# klmag2gend-b031.net
KiCad netlist of a schematic drawn in Altium Designer
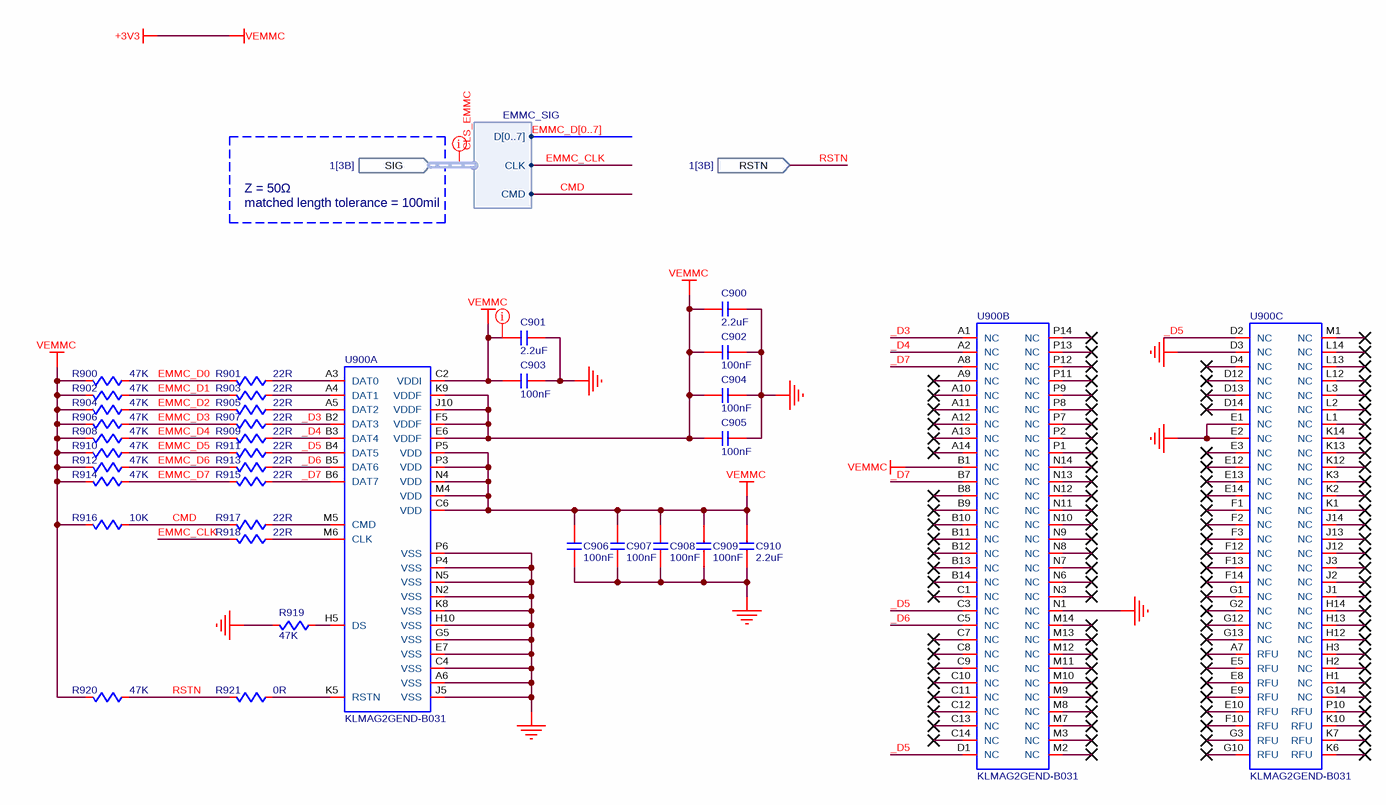
[diagram p0: klmag2gend-b031.SchDoc]

(export (version "E")
  (design (tool "Eeschema 10.0.6"))
  (components
    (comp (ref "C900")
      (value "2.2uF")
      (footprint "mw:C0603")
      (fields (field (name "VOLTAGE") "25V") (field (name "Comment") "C-NOMO"))
      (libsource (lib "mw") (part "C-NOMO"))
    )
    (comp (ref "C901")
      (value "2.2uF")
      (footprint "mw:C0603")
      (fields (field (name "VOLTAGE") "25V") (field (name "Comment") "C-NOMO"))
      (libsource (lib "mw") (part "C-NOMO"))
    )
    (comp (ref "C902")
      (value "100nF")
      (footprint "mw:C0402")
      (fields (field (name "VOLTAGE") "25V") (field (name "Comment") "C-NOMO"))
      (libsource (lib "mw") (part "C-NOMO"))
    )
    (comp (ref "C903")
      (value "100nF")
      (footprint "mw:C0402")
      (fields (field (name "VOLTAGE") "25V") (field (name "Comment") "C-NOMO"))
      (libsource (lib "mw") (part "C-NOMO"))
    )
    (comp (ref "C904")
      (value "100nF")
      (footprint "mw:C0402")
      (fields (field (name "VOLTAGE") "25V") (field (name "Comment") "C-NOMO"))
      (libsource (lib "mw") (part "C-NOMO"))
    )
    (comp (ref "C905")
      (value "100nF")
      (footprint "mw:C0402")
      (fields (field (name "VOLTAGE") "25V") (field (name "Comment") "C-NOMO"))
      (libsource (lib "mw") (part "C-NOMO"))
    )
    (comp (ref "C906")
      (value "100nF")
      (footprint "mw:C0402")
      (fields (field (name "VOLTAGE") "25V") (field (name "Comment") "C-NOMO"))
      (libsource (lib "mw") (part "C-NOMO"))
    )
    (comp (ref "C907")
      (value "100nF")
      (footprint "mw:C0402")
      (fields (field (name "VOLTAGE") "25V") (field (name "Comment") "C-NOMO"))
      (libsource (lib "mw") (part "C-NOMO"))
    )
    (comp (ref "C908")
      (value "100nF")
      (footprint "mw:C0402")
      (fields (field (name "VOLTAGE") "25V") (field (name "Comment") "C-NOMO"))
      (libsource (lib "mw") (part "C-NOMO"))
    )
    (comp (ref "C909")
      (value "100nF")
      (footprint "mw:C0402")
      (fields (field (name "VOLTAGE") "25V") (field (name "Comment") "C-NOMO"))
      (libsource (lib "mw") (part "C-NOMO"))
    )
    (comp (ref "C910")
      (value "2.2uF")
      (footprint "mw:C0603")
      (fields (field (name "VOLTAGE") "25V") (field (name "Comment") "C-NOMO"))
      (libsource (lib "mw") (part "C-NOMO"))
    )
    (comp (ref "R900")
      (value "47K")
      (footprint "mw:R0402")
      (fields (field (name "Comment") "R"))
      (libsource (lib "mw") (part "R"))
    )
    (comp (ref "R901")
      (value "22R")
      (footprint "mw:R0402")
      (fields (field (name "Comment") "R"))
      (libsource (lib "mw") (part "R"))
    )
    (comp (ref "R902")
      (value "47K")
      (footprint "mw:R0402")
      (fields (field (name "Comment") "R"))
      (libsource (lib "mw") (part "R"))
    )
    (comp (ref "R903")
      (value "22R")
      (footprint "mw:R0402")
      (fields (field (name "Comment") "R"))
      (libsource (lib "mw") (part "R"))
    )
    (comp (ref "R904")
      (value "47K")
      (footprint "mw:R0402")
      (fields (field (name "Comment") "R"))
      (libsource (lib "mw") (part "R"))
    )
    (comp (ref "R905")
      (value "22R")
      (footprint "mw:R0402")
      (fields (field (name "Comment") "R"))
      (libsource (lib "mw") (part "R"))
    )
    (comp (ref "R906")
      (value "47K")
      (footprint "mw:R0402")
      (fields (field (name "Comment") "R"))
      (libsource (lib "mw") (part "R"))
    )
    (comp (ref "R907")
      (value "22R")
      (footprint "mw:R0402")
      (fields (field (name "Comment") "R"))
      (libsource (lib "mw") (part "R"))
    )
    (comp (ref "R908")
      (value "47K")
      (footprint "mw:R0402")
      (fields (field (name "Comment") "R"))
      (libsource (lib "mw") (part "R"))
    )
    (comp (ref "R909")
      (value "22R")
      (footprint "mw:R0402")
      (fields (field (name "Comment") "R"))
      (libsource (lib "mw") (part "R"))
    )
    (comp (ref "R910")
      (value "47K")
      (footprint "mw:R0402")
      (fields (field (name "Comment") "R"))
      (libsource (lib "mw") (part "R"))
    )
    (comp (ref "R911")
      (value "22R")
      (footprint "mw:R0402")
      (fields (field (name "Comment") "R"))
      (libsource (lib "mw") (part "R"))
    )
    (comp (ref "R912")
      (value "47K")
      (footprint "mw:R0402")
      (fields (field (name "Comment") "R"))
      (libsource (lib "mw") (part "R"))
    )
    (comp (ref "R913")
      (value "22R")
      (footprint "mw:R0402")
      (fields (field (name "Comment") "R"))
      (libsource (lib "mw") (part "R"))
    )
    (comp (ref "R914")
      (value "47K")
      (footprint "mw:R0402")
      (fields (field (name "Comment") "R"))
      (libsource (lib "mw") (part "R"))
    )
    (comp (ref "R915")
      (value "22R")
      (footprint "mw:R0402")
      (fields (field (name "Comment") "R"))
      (libsource (lib "mw") (part "R"))
    )
    (comp (ref "R916")
      (value "10K")
      (footprint "mw:R0402")
      (fields (field (name "Comment") "R"))
      (libsource (lib "mw") (part "R"))
    )
    (comp (ref "R917")
      (value "22R")
      (footprint "mw:R0402")
      (fields (field (name "Comment") "R"))
      (libsource (lib "mw") (part "R"))
    )
    (comp (ref "R918")
      (value "22R")
      (footprint "mw:R0402")
      (fields (field (name "Comment") "R"))
      (libsource (lib "mw") (part "R"))
    )
    (comp (ref "R919")
      (value "47K")
      (footprint "mw:R0402")
      (fields (field (name "Comment") "R"))
      (libsource (lib "mw") (part "R"))
    )
    (comp (ref "R920")
      (value "47K")
      (footprint "mw:R0402")
      (fields (field (name "Comment") "R"))
      (libsource (lib "mw") (part "R"))
    )
    (comp (ref "R921")
      (value "0R")
      (footprint "mw:R0402")
      (fields (field (name "Comment") "R"))
      (libsource (lib "mw") (part "R"))
    )
    (comp (ref "U900")
      (value "KLMAG2GEND-B031")
      (footprint "mw:KLMAG2GEND-B031")
      (description "EMMC")
      (libsource (lib "mw") (part "KLMAG2GEND-B031"))
    )
  )
  (nets
    (net (code "2") (name "+3V3") (class "Default")
      (node (ref "C900") (pin "2") (pinfunction "2_2") (pintype "passive"))
      (node (ref "C901") (pin "2") (pinfunction "2_2") (pintype "passive"))
      (node (ref "C902") (pin "2") (pinfunction "2_2") (pintype "passive"))
      (node (ref "C903") (pin "2") (pinfunction "2_2") (pintype "passive"))
      (node (ref "C904") (pin "2") (pinfunction "2_2") (pintype "passive"))
      (node (ref "C905") (pin "2") (pinfunction "2_2") (pintype "passive"))
      (node (ref "C906") (pin "2") (pinfunction "2_2") (pintype "passive"))
      (node (ref "C907") (pin "2") (pinfunction "2_2") (pintype "passive"))
      (node (ref "C908") (pin "2") (pinfunction "2_2") (pintype "passive"))
      (node (ref "C909") (pin "2") (pinfunction "2_2") (pintype "passive"))
      (node (ref "C910") (pin "2") (pinfunction "2_2") (pintype "passive"))
      (node (ref "R900") (pin "1") (pinfunction "1_1") (pintype "passive"))
      (node (ref "R902") (pin "1") (pinfunction "1_1") (pintype "passive"))
      (node (ref "R904") (pin "1") (pinfunction "1_1") (pintype "passive"))
      (node (ref "R906") (pin "1") (pinfunction "1_1") (pintype "passive"))
      (node (ref "R908") (pin "1") (pinfunction "1_1") (pintype "passive"))
      (node (ref "R910") (pin "1") (pinfunction "1_1") (pintype "passive"))
      (node (ref "R912") (pin "1") (pinfunction "1_1") (pintype "passive"))
      (node (ref "R914") (pin "1") (pinfunction "1_1") (pintype "passive"))
      (node (ref "R916") (pin "1") (pinfunction "1_1") (pintype "passive"))
      (node (ref "R920") (pin "1") (pinfunction "1_1") (pintype "passive"))
      (node (ref "U900") (pin "B1") (pinfunction "NC_B1") (pintype "passive"))
      (node (ref "U900") (pin "C2") (pinfunction "VDDI_C2") (pintype "passive"))
      (node (ref "U900") (pin "C6") (pinfunction "VDD_C6") (pintype "passive"))
      (node (ref "U900") (pin "E6") (pinfunction "VDDF_E6") (pintype "passive"))
      (node (ref "U900") (pin "F5") (pinfunction "VDDF_F5") (pintype "passive"))
      (node (ref "U900") (pin "J10") (pinfunction "VDDF_J10") (pintype "passive"))
      (node (ref "U900") (pin "K9") (pinfunction "VDDF_K9") (pintype "passive"))
      (node (ref "U900") (pin "M4") (pinfunction "VDD_M4") (pintype "passive"))
      (node (ref "U900") (pin "N4") (pinfunction "VDD_N4") (pintype "passive"))
      (node (ref "U900") (pin "P3") (pinfunction "VDD_P3") (pintype "passive"))
      (node (ref "U900") (pin "P5") (pinfunction "VDD_P5") (pintype "passive"))
    )
    (net (code "3") (name "/CMD") (class "Default")
      (node (ref "R916") (pin "2") (pinfunction "2_2") (pintype "passive"))
      (node (ref "R917") (pin "1") (pinfunction "1_1") (pintype "passive"))
    )
    (net (code "4") (name "/EMMC_CLK") (class "Default")
      (node (ref "R918") (pin "1") (pinfunction "1_1") (pintype "passive"))
    )
    (net (code "5") (name "/EMMC_D0") (class "Default")
      (node (ref "R900") (pin "2") (pinfunction "2_2") (pintype "passive"))
      (node (ref "R901") (pin "1") (pinfunction "1_1") (pintype "passive"))
    )
    (net (code "6") (name "/EMMC_D1") (class "Default")
      (node (ref "R902") (pin "2") (pinfunction "2_2") (pintype "passive"))
      (node (ref "R903") (pin "1") (pinfunction "1_1") (pintype "passive"))
    )
    (net (code "7") (name "/EMMC_D2") (class "Default")
      (node (ref "R904") (pin "2") (pinfunction "2_2") (pintype "passive"))
      (node (ref "R905") (pin "1") (pinfunction "1_1") (pintype "passive"))
    )
    (net (code "8") (name "/EMMC_D3") (class "Default")
      (node (ref "R906") (pin "2") (pinfunction "2_2") (pintype "passive"))
      (node (ref "R907") (pin "1") (pinfunction "1_1") (pintype "passive"))
    )
    (net (code "9") (name "/EMMC_D4") (class "Default")
      (node (ref "R908") (pin "2") (pinfunction "2_2") (pintype "passive"))
      (node (ref "R909") (pin "1") (pinfunction "1_1") (pintype "passive"))
    )
    (net (code "10") (name "/EMMC_D5") (class "Default")
      (node (ref "R910") (pin "2") (pinfunction "2_2") (pintype "passive"))
      (node (ref "R911") (pin "1") (pinfunction "1_1") (pintype "passive"))
    )
    (net (code "11") (name "/EMMC_D6") (class "Default")
      (node (ref "R912") (pin "2") (pinfunction "2_2") (pintype "passive"))
      (node (ref "R913") (pin "1") (pinfunction "1_1") (pintype "passive"))
    )
    (net (code "12") (name "/EMMC_D7") (class "Default")
      (node (ref "R914") (pin "2") (pinfunction "2_2") (pintype "passive"))
      (node (ref "R915") (pin "1") (pinfunction "1_1") (pintype "passive"))
    )
    (net (code "13") (name "/RSTN") (class "Default")
      (node (ref "R920") (pin "2") (pinfunction "2_2") (pintype "passive"))
      (node (ref "R921") (pin "1") (pinfunction "1_1") (pintype "passive"))
    )
    (net (code "15") (name "/_D3") (class "Default")
      (node (ref "R907") (pin "2") (pinfunction "2_2") (pintype "passive"))
      (node (ref "U900") (pin "A1") (pinfunction "NC_A1") (pintype "passive"))
      (node (ref "U900") (pin "B2") (pinfunction "DAT3_B2") (pintype "passive"))
    )
    (net (code "16") (name "/_D4") (class "Default")
      (node (ref "R909") (pin "2") (pinfunction "2_2") (pintype "passive"))
      (node (ref "U900") (pin "A2") (pinfunction "NC_A2") (pintype "passive"))
      (node (ref "U900") (pin "B3") (pinfunction "DAT4_B3") (pintype "passive"))
    )
    (net (code "17") (name "/_D5") (class "Default")
      (node (ref "R911") (pin "2") (pinfunction "2_2") (pintype "passive"))
      (node (ref "U900") (pin "B4") (pinfunction "DAT5_B4") (pintype "passive"))
      (node (ref "U900") (pin "C3") (pinfunction "NC_C3") (pintype "passive"))
      (node (ref "U900") (pin "D1") (pinfunction "NC_D1") (pintype "passive"))
      (node (ref "U900") (pin "D2") (pinfunction "NC_D2") (pintype "passive"))
    )
    (net (code "18") (name "/_D6") (class "Default")
      (node (ref "R913") (pin "2") (pinfunction "2_2") (pintype "passive"))
      (node (ref "U900") (pin "B5") (pinfunction "DAT6_B5") (pintype "passive"))
      (node (ref "U900") (pin "C5") (pinfunction "NC_C5") (pintype "passive"))
    )
    (net (code "19") (name "/_D7") (class "Default")
      (node (ref "R915") (pin "2") (pinfunction "2_2") (pintype "passive"))
      (node (ref "U900") (pin "A8") (pinfunction "NC_A8") (pintype "passive"))
      (node (ref "U900") (pin "B6") (pinfunction "DAT7_B6") (pintype "passive"))
      (node (ref "U900") (pin "B7") (pinfunction "NC_B7") (pintype "passive"))
    )
    (net (code "21") (name "GND") (class "Default")
      (node (ref "C900") (pin "1") (pinfunction "1_1") (pintype "passive"))
      (node (ref "C901") (pin "1") (pinfunction "1_1") (pintype "passive"))
      (node (ref "C902") (pin "1") (pinfunction "1_1") (pintype "passive"))
      (node (ref "C903") (pin "1") (pinfunction "1_1") (pintype "passive"))
      (node (ref "C904") (pin "1") (pinfunction "1_1") (pintype "passive"))
      (node (ref "C905") (pin "1") (pinfunction "1_1") (pintype "passive"))
      (node (ref "C906") (pin "1") (pinfunction "1_1") (pintype "passive"))
      (node (ref "C907") (pin "1") (pinfunction "1_1") (pintype "passive"))
      (node (ref "C908") (pin "1") (pinfunction "1_1") (pintype "passive"))
      (node (ref "C909") (pin "1") (pinfunction "1_1") (pintype "passive"))
      (node (ref "C910") (pin "1") (pinfunction "1_1") (pintype "passive"))
      (node (ref "R919") (pin "1") (pinfunction "1_1") (pintype "passive"))
      (node (ref "U900") (pin "A6") (pinfunction "VSS_A6") (pintype "passive"))
      (node (ref "U900") (pin "C4") (pinfunction "VSS_C4") (pintype "passive"))
      (node (ref "U900") (pin "D3") (pinfunction "NC_D3") (pintype "passive"))
      (node (ref "U900") (pin "E1") (pinfunction "NC_E1") (pintype "passive"))
      (node (ref "U900") (pin "E2") (pinfunction "NC_E2") (pintype "passive"))
      (node (ref "U900") (pin "E7") (pinfunction "VSS_E7") (pintype "passive"))
      (node (ref "U900") (pin "G5") (pinfunction "VSS_G5") (pintype "passive"))
      (node (ref "U900") (pin "H10") (pinfunction "VSS_H10") (pintype "passive"))
      (node (ref "U900") (pin "J5") (pinfunction "VSS_J5") (pintype "passive"))
      (node (ref "U900") (pin "K8") (pinfunction "VSS_K8") (pintype "passive"))
      (node (ref "U900") (pin "N1") (pinfunction "NC_N1") (pintype "passive"))
      (node (ref "U900") (pin "N2") (pinfunction "VSS_N2") (pintype "passive"))
      (node (ref "U900") (pin "N5") (pinfunction "VSS_N5") (pintype "passive"))
      (node (ref "U900") (pin "P4") (pinfunction "VSS_P4") (pintype "passive"))
      (node (ref "U900") (pin "P6") (pinfunction "VSS_P6") (pintype "passive"))
    )
    (net (code "22") (name "Net-(U900A-CLK)") (class "Default")
      (node (ref "R918") (pin "2") (pinfunction "2_2") (pintype "passive"))
      (node (ref "U900") (pin "M6") (pinfunction "CLK_M6") (pintype "passive"))
    )
    (net (code "23") (name "Net-(U900A-CMD)") (class "Default")
      (node (ref "R917") (pin "2") (pinfunction "2_2") (pintype "passive"))
      (node (ref "U900") (pin "M5") (pinfunction "CMD_M5") (pintype "passive"))
    )
    (net (code "24") (name "Net-(U900A-DAT0)") (class "Default")
      (node (ref "R901") (pin "2") (pinfunction "2_2") (pintype "passive"))
      (node (ref "U900") (pin "A3") (pinfunction "DAT0_A3") (pintype "passive"))
    )
    (net (code "25") (name "Net-(U900A-DAT1)") (class "Default")
      (node (ref "R903") (pin "2") (pinfunction "2_2") (pintype "passive"))
      (node (ref "U900") (pin "A4") (pinfunction "DAT1_A4") (pintype "passive"))
    )
    (net (code "26") (name "Net-(U900A-DAT2)") (class "Default")
      (node (ref "R905") (pin "2") (pinfunction "2_2") (pintype "passive"))
      (node (ref "U900") (pin "A5") (pinfunction "DAT2_A5") (pintype "passive"))
    )
    (net (code "27") (name "Net-(U900A-DS)") (class "Default")
      (node (ref "R919") (pin "2") (pinfunction "2_2") (pintype "passive"))
      (node (ref "U900") (pin "H5") (pinfunction "DS_H5") (pintype "passive"))
    )
    (net (code "28") (name "Net-(U900A-RSTN)") (class "Default")
      (node (ref "R921") (pin "2") (pinfunction "2_2") (pintype "passive"))
      (node (ref "U900") (pin "K5") (pinfunction "RSTN_K5") (pintype "passive"))
    )
    (net (code "29") (name "unconnected-(U900B-NC-PadA9)") (class "Default")
      (node (ref "U900") (pin "A9") (pinfunction "NC_A9") (pintype "passive+no_connect"))
    )
    (net (code "30") (name "unconnected-(U900B-NC-PadA10)") (class "Default")
      (node (ref "U900") (pin "A10") (pinfunction "NC_A10") (pintype "passive+no_connect"))
    )
    (net (code "31") (name "unconnected-(U900B-NC-PadA11)") (class "Default")
      (node (ref "U900") (pin "A11") (pinfunction "NC_A11") (pintype "passive+no_connect"))
    )
    (net (code "32") (name "unconnected-(U900B-NC-PadA12)") (class "Default")
      (node (ref "U900") (pin "A12") (pinfunction "NC_A12") (pintype "passive+no_connect"))
    )
    (net (code "33") (name "unconnected-(U900B-NC-PadA13)") (class "Default")
      (node (ref "U900") (pin "A13") (pinfunction "NC_A13") (pintype "passive+no_connect"))
    )
    (net (code "34") (name "unconnected-(U900B-NC-PadA14)") (class "Default")
      (node (ref "U900") (pin "A14") (pinfunction "NC_A14") (pintype "passive+no_connect"))
    )
    (net (code "35") (name "unconnected-(U900B-NC-PadB8)") (class "Default")
      (node (ref "U900") (pin "B8") (pinfunction "NC_B8") (pintype "passive+no_connect"))
    )
    (net (code "36") (name "unconnected-(U900B-NC-PadB9)") (class "Default")
      (node (ref "U900") (pin "B9") (pinfunction "NC_B9") (pintype "passive+no_connect"))
    )
    (net (code "37") (name "unconnected-(U900B-NC-PadB10)") (class "Default")
      (node (ref "U900") (pin "B10") (pinfunction "NC_B10") (pintype "passive+no_connect"))
    )
    (net (code "38") (name "unconnected-(U900B-NC-PadB11)") (class "Default")
      (node (ref "U900") (pin "B11") (pinfunction "NC_B11") (pintype "passive+no_connect"))
    )
    (net (code "39") (name "unconnected-(U900B-NC-PadB12)") (class "Default")
      (node (ref "U900") (pin "B12") (pinfunction "NC_B12") (pintype "passive+no_connect"))
    )
    (net (code "40") (name "unconnected-(U900B-NC-PadB13)") (class "Default")
      (node (ref "U900") (pin "B13") (pinfunction "NC_B13") (pintype "passive+no_connect"))
    )
    (net (code "41") (name "unconnected-(U900B-NC-PadB14)") (class "Default")
      (node (ref "U900") (pin "B14") (pinfunction "NC_B14") (pintype "passive+no_connect"))
    )
    (net (code "42") (name "unconnected-(U900B-NC-PadC1)") (class "Default")
      (node (ref "U900") (pin "C1") (pinfunction "NC_C1") (pintype "passive+no_connect"))
    )
    (net (code "43") (name "unconnected-(U900B-NC-PadC7)") (class "Default")
      (node (ref "U900") (pin "C7") (pinfunction "NC_C7") (pintype "passive+no_connect"))
    )
    (net (code "44") (name "unconnected-(U900B-NC-PadC8)") (class "Default")
      (node (ref "U900") (pin "C8") (pinfunction "NC_C8") (pintype "passive+no_connect"))
    )
    (net (code "45") (name "unconnected-(U900B-NC-PadC9)") (class "Default")
      (node (ref "U900") (pin "C9") (pinfunction "NC_C9") (pintype "passive+no_connect"))
    )
    (net (code "46") (name "unconnected-(U900B-NC-PadC10)") (class "Default")
      (node (ref "U900") (pin "C10") (pinfunction "NC_C10") (pintype "passive+no_connect"))
    )
    (net (code "47") (name "unconnected-(U900B-NC-PadC11)") (class "Default")
      (node (ref "U900") (pin "C11") (pinfunction "NC_C11") (pintype "passive+no_connect"))
    )
    (net (code "48") (name "unconnected-(U900B-NC-PadC12)") (class "Default")
      (node (ref "U900") (pin "C12") (pinfunction "NC_C12") (pintype "passive+no_connect"))
    )
    (net (code "49") (name "unconnected-(U900B-NC-PadC13)") (class "Default")
      (node (ref "U900") (pin "C13") (pinfunction "NC_C13") (pintype "passive+no_connect"))
    )
    (net (code "50") (name "unconnected-(U900B-NC-PadC14)") (class "Default")
      (node (ref "U900") (pin "C14") (pinfunction "NC_C14") (pintype "passive+no_connect"))
    )
    (net (code "51") (name "unconnected-(U900B-NC-PadM2)") (class "Default")
      (node (ref "U900") (pin "M2") (pinfunction "NC_M2") (pintype "passive+no_connect"))
    )
    (net (code "52") (name "unconnected-(U900B-NC-PadM3)") (class "Default")
      (node (ref "U900") (pin "M3") (pinfunction "NC_M3") (pintype "passive+no_connect"))
    )
    (net (code "53") (name "unconnected-(U900B-NC-PadM7)") (class "Default")
      (node (ref "U900") (pin "M7") (pinfunction "NC_M7") (pintype "passive+no_connect"))
    )
    (net (code "54") (name "unconnected-(U900B-NC-PadM8)") (class "Default")
      (node (ref "U900") (pin "M8") (pinfunction "NC_M8") (pintype "passive+no_connect"))
    )
    (net (code "55") (name "unconnected-(U900B-NC-PadM9)") (class "Default")
      (node (ref "U900") (pin "M9") (pinfunction "NC_M9") (pintype "passive+no_connect"))
    )
    (net (code "56") (name "unconnected-(U900B-NC-PadM10)") (class "Default")
      (node (ref "U900") (pin "M10") (pinfunction "NC_M10") (pintype "passive+no_connect"))
    )
    (net (code "57") (name "unconnected-(U900B-NC-PadM11)") (class "Default")
      (node (ref "U900") (pin "M11") (pinfunction "NC_M11") (pintype "passive+no_connect"))
    )
    (net (code "58") (name "unconnected-(U900B-NC-PadM12)") (class "Default")
      (node (ref "U900") (pin "M12") (pinfunction "NC_M12") (pintype "passive+no_connect"))
    )
    (net (code "59") (name "unconnected-(U900B-NC-PadM13)") (class "Default")
      (node (ref "U900") (pin "M13") (pinfunction "NC_M13") (pintype "passive+no_connect"))
    )
    (net (code "60") (name "unconnected-(U900B-NC-PadM14)") (class "Default")
      (node (ref "U900") (pin "M14") (pinfunction "NC_M14") (pintype "passive+no_connect"))
    )
    (net (code "61") (name "unconnected-(U900B-NC-PadN3)") (class "Default")
      (node (ref "U900") (pin "N3") (pinfunction "NC_N3") (pintype "passive+no_connect"))
    )
    (net (code "62") (name "unconnected-(U900B-NC-PadN6)") (class "Default")
      (node (ref "U900") (pin "N6") (pinfunction "NC_N6") (pintype "passive+no_connect"))
    )
    (net (code "63") (name "unconnected-(U900B-NC-PadN7)") (class "Default")
      (node (ref "U900") (pin "N7") (pinfunction "NC_N7") (pintype "passive+no_connect"))
    )
    (net (code "64") (name "unconnected-(U900B-NC-PadN8)") (class "Default")
      (node (ref "U900") (pin "N8") (pinfunction "NC_N8") (pintype "passive+no_connect"))
    )
    (net (code "65") (name "unconnected-(U900B-NC-PadN9)") (class "Default")
      (node (ref "U900") (pin "N9") (pinfunction "NC_N9") (pintype "passive+no_connect"))
    )
    (net (code "66") (name "unconnected-(U900B-NC-PadN10)") (class "Default")
      (node (ref "U900") (pin "N10") (pinfunction "NC_N10") (pintype "passive+no_connect"))
    )
    (net (code "67") (name "unconnected-(U900B-NC-PadN11)") (class "Default")
      (node (ref "U900") (pin "N11") (pinfunction "NC_N11") (pintype "passive+no_connect"))
    )
    (net (code "68") (name "unconnected-(U900B-NC-PadN12)") (class "Default")
      (node (ref "U900") (pin "N12") (pinfunction "NC_N12") (pintype "passive+no_connect"))
    )
    (net (code "69") (name "unconnected-(U900B-NC-PadN13)") (class "Default")
      (node (ref "U900") (pin "N13") (pinfunction "NC_N13") (pintype "passive+no_connect"))
    )
    (net (code "70") (name "unconnected-(U900B-NC-PadN14)") (class "Default")
      (node (ref "U900") (pin "N14") (pinfunction "NC_N14") (pintype "passive+no_connect"))
    )
    (net (code "71") (name "unconnected-(U900B-NC-PadP1)") (class "Default")
      (node (ref "U900") (pin "P1") (pinfunction "NC_P1") (pintype "passive+no_connect"))
    )
    (net (code "72") (name "unconnected-(U900B-NC-PadP2)") (class "Default")
      (node (ref "U900") (pin "P2") (pinfunction "NC_P2") (pintype "passive+no_connect"))
    )
    (net (code "73") (name "unconnected-(U900B-NC-PadP7)") (class "Default")
      (node (ref "U900") (pin "P7") (pinfunction "NC_P7") (pintype "passive+no_connect"))
    )
    (net (code "74") (name "unconnected-(U900B-NC-PadP8)") (class "Default")
      (node (ref "U900") (pin "P8") (pinfunction "NC_P8") (pintype "passive+no_connect"))
    )
    (net (code "75") (name "unconnected-(U900B-NC-PadP9)") (class "Default")
      (node (ref "U900") (pin "P9") (pinfunction "NC_P9") (pintype "passive+no_connect"))
    )
    (net (code "76") (name "unconnected-(U900B-NC-PadP11)") (class "Default")
      (node (ref "U900") (pin "P11") (pinfunction "NC_P11") (pintype "passive+no_connect"))
    )
    (net (code "77") (name "unconnected-(U900B-NC-PadP12)") (class "Default")
      (node (ref "U900") (pin "P12") (pinfunction "NC_P12") (pintype "passive+no_connect"))
    )
    (net (code "78") (name "unconnected-(U900B-NC-PadP13)") (class "Default")
      (node (ref "U900") (pin "P13") (pinfunction "NC_P13") (pintype "passive+no_connect"))
    )
    (net (code "79") (name "unconnected-(U900B-NC-PadP14)") (class "Default")
      (node (ref "U900") (pin "P14") (pinfunction "NC_P14") (pintype "passive+no_connect"))
    )
    (net (code "80") (name "unconnected-(U900C-NC-PadD4)") (class "Default")
      (node (ref "U900") (pin "D4") (pinfunction "NC_D4") (pintype "passive+no_connect"))
    )
    (net (code "81") (name "unconnected-(U900C-NC-PadD12)") (class "Default")
      (node (ref "U900") (pin "D12") (pinfunction "NC_D12") (pintype "passive+no_connect"))
    )
    (net (code "82") (name "unconnected-(U900C-NC-PadD13)") (class "Default")
      (node (ref "U900") (pin "D13") (pinfunction "NC_D13") (pintype "passive+no_connect"))
    )
    (net (code "83") (name "unconnected-(U900C-NC-PadD14)") (class "Default")
      (node (ref "U900") (pin "D14") (pinfunction "NC_D14") (pintype "passive+no_connect"))
    )
    (net (code "84") (name "unconnected-(U900C-NC-PadE3)") (class "Default")
      (node (ref "U900") (pin "E3") (pinfunction "NC_E3") (pintype "passive+no_connect"))
    )
    (net (code "85") (name "unconnected-(U900C-NC-PadE12)") (class "Default")
      (node (ref "U900") (pin "E12") (pinfunction "NC_E12") (pintype "passive+no_connect"))
    )
    (net (code "86") (name "unconnected-(U900C-NC-PadE13)") (class "Default")
      (node (ref "U900") (pin "E13") (pinfunction "NC_E13") (pintype "passive+no_connect"))
    )
    (net (code "87") (name "unconnected-(U900C-NC-PadE14)") (class "Default")
      (node (ref "U900") (pin "E14") (pinfunction "NC_E14") (pintype "passive+no_connect"))
    )
    (net (code "88") (name "unconnected-(U900C-NC-PadF1)") (class "Default")
      (node (ref "U900") (pin "F1") (pinfunction "NC_F1") (pintype "passive+no_connect"))
    )
    (net (code "89") (name "unconnected-(U900C-NC-PadF2)") (class "Default")
      (node (ref "U900") (pin "F2") (pinfunction "NC_F2") (pintype "passive+no_connect"))
    )
    (net (code "90") (name "unconnected-(U900C-NC-PadF3)") (class "Default")
      (node (ref "U900") (pin "F3") (pinfunction "NC_F3") (pintype "passive+no_connect"))
    )
    (net (code "91") (name "unconnected-(U900C-NC-PadF12)") (class "Default")
      (node (ref "U900") (pin "F12") (pinfunction "NC_F12") (pintype "passive+no_connect"))
    )
    (net (code "92") (name "unconnected-(U900C-NC-PadF13)") (class "Default")
      (node (ref "U900") (pin "F13") (pinfunction "NC_F13") (pintype "passive+no_connect"))
    )
    (net (code "93") (name "unconnected-(U900C-NC-PadF14)") (class "Default")
      (node (ref "U900") (pin "F14") (pinfunction "NC_F14") (pintype "passive+no_connect"))
    )
    (net (code "94") (name "unconnected-(U900C-NC-PadG1)") (class "Default")
      (node (ref "U900") (pin "G1") (pinfunction "NC_G1") (pintype "passive+no_connect"))
    )
    (net (code "95") (name "unconnected-(U900C-NC-PadG2)") (class "Default")
      (node (ref "U900") (pin "G2") (pinfunction "NC_G2") (pintype "passive+no_connect"))
    )
    (net (code "96") (name "unconnected-(U900C-NC-PadG12)") (class "Default")
      (node (ref "U900") (pin "G12") (pinfunction "NC_G12") (pintype "passive+no_connect"))
    )
    (net (code "97") (name "unconnected-(U900C-NC-PadG13)") (class "Default")
      (node (ref "U900") (pin "G13") (pinfunction "NC_G13") (pintype "passive+no_connect"))
    )
    (net (code "98") (name "unconnected-(U900C-NC-PadG14)") (class "Default")
      (node (ref "U900") (pin "G14") (pinfunction "NC_G14") (pintype "passive+no_connect"))
    )
    (net (code "99") (name "unconnected-(U900C-NC-PadH1)") (class "Default")
      (node (ref "U900") (pin "H1") (pinfunction "NC_H1") (pintype "passive+no_connect"))
    )
    (net (code "100") (name "unconnected-(U900C-NC-PadH2)") (class "Default")
      (node (ref "U900") (pin "H2") (pinfunction "NC_H2") (pintype "passive+no_connect"))
    )
    (net (code "101") (name "unconnected-(U900C-NC-PadH3)") (class "Default")
      (node (ref "U900") (pin "H3") (pinfunction "NC_H3") (pintype "passive+no_connect"))
    )
    (net (code "102") (name "unconnected-(U900C-NC-PadH12)") (class "Default")
      (node (ref "U900") (pin "H12") (pinfunction "NC_H12") (pintype "passive+no_connect"))
    )
    (net (code "103") (name "unconnected-(U900C-NC-PadH13)") (class "Default")
      (node (ref "U900") (pin "H13") (pinfunction "NC_H13") (pintype "passive+no_connect"))
    )
    (net (code "104") (name "unconnected-(U900C-NC-PadH14)") (class "Default")
      (node (ref "U900") (pin "H14") (pinfunction "NC_H14") (pintype "passive+no_connect"))
    )
    (net (code "105") (name "unconnected-(U900C-NC-PadJ1)") (class "Default")
      (node (ref "U900") (pin "J1") (pinfunction "NC_J1") (pintype "passive+no_connect"))
    )
    (net (code "106") (name "unconnected-(U900C-NC-PadJ2)") (class "Default")
      (node (ref "U900") (pin "J2") (pinfunction "NC_J2") (pintype "passive+no_connect"))
    )
    (net (code "107") (name "unconnected-(U900C-NC-PadJ3)") (class "Default")
      (node (ref "U900") (pin "J3") (pinfunction "NC_J3") (pintype "passive+no_connect"))
    )
    (net (code "108") (name "unconnected-(U900C-NC-PadJ12)") (class "Default")
      (node (ref "U900") (pin "J12") (pinfunction "NC_J12") (pintype "passive+no_connect"))
    )
    (net (code "109") (name "unconnected-(U900C-NC-PadJ13)") (class "Default")
      (node (ref "U900") (pin "J13") (pinfunction "NC_J13") (pintype "passive+no_connect"))
    )
    (net (code "110") (name "unconnected-(U900C-NC-PadJ14)") (class "Default")
      (node (ref "U900") (pin "J14") (pinfunction "NC_J14") (pintype "passive+no_connect"))
    )
    (net (code "111") (name "unconnected-(U900C-NC-PadK1)") (class "Default")
      (node (ref "U900") (pin "K1") (pinfunction "NC_K1") (pintype "passive+no_connect"))
    )
    (net (code "112") (name "unconnected-(U900C-NC-PadK2)") (class "Default")
      (node (ref "U900") (pin "K2") (pinfunction "NC_K2") (pintype "passive+no_connect"))
    )
    (net (code "113") (name "unconnected-(U900C-NC-PadK3)") (class "Default")
      (node (ref "U900") (pin "K3") (pinfunction "NC_K3") (pintype "passive+no_connect"))
    )
    (net (code "114") (name "unconnected-(U900C-NC-PadK12)") (class "Default")
      (node (ref "U900") (pin "K12") (pinfunction "NC_K12") (pintype "passive+no_connect"))
    )
    (net (code "115") (name "unconnected-(U900C-NC-PadK13)") (class "Default")
      (node (ref "U900") (pin "K13") (pinfunction "NC_K13") (pintype "passive+no_connect"))
    )
    (net (code "116") (name "unconnected-(U900C-NC-PadK14)") (class "Default")
      (node (ref "U900") (pin "K14") (pinfunction "NC_K14") (pintype "passive+no_connect"))
    )
    (net (code "117") (name "unconnected-(U900C-NC-PadL1)") (class "Default")
      (node (ref "U900") (pin "L1") (pinfunction "NC_L1") (pintype "passive+no_connect"))
    )
    (net (code "118") (name "unconnected-(U900C-NC-PadL2)") (class "Default")
      (node (ref "U900") (pin "L2") (pinfunction "NC_L2") (pintype "passive+no_connect"))
    )
    (net (code "119") (name "unconnected-(U900C-NC-PadL3)") (class "Default")
      (node (ref "U900") (pin "L3") (pinfunction "NC_L3") (pintype "passive+no_connect"))
    )
    (net (code "120") (name "unconnected-(U900C-NC-PadL12)") (class "Default")
      (node (ref "U900") (pin "L12") (pinfunction "NC_L12") (pintype "passive+no_connect"))
    )
    (net (code "121") (name "unconnected-(U900C-NC-PadL13)") (class "Default")
      (node (ref "U900") (pin "L13") (pinfunction "NC_L13") (pintype "passive+no_connect"))
    )
    (net (code "122") (name "unconnected-(U900C-NC-PadL14)") (class "Default")
      (node (ref "U900") (pin "L14") (pinfunction "NC_L14") (pintype "passive+no_connect"))
    )
    (net (code "123") (name "unconnected-(U900C-NC-PadM1)") (class "Default")
      (node (ref "U900") (pin "M1") (pinfunction "NC_M1") (pintype "passive+no_connect"))
    )
    (net (code "124") (name "unconnected-(U900C-RFU-PadA7)") (class "Default")
      (node (ref "U900") (pin "A7") (pinfunction "RFU_A7") (pintype "passive+no_connect"))
    )
    (net (code "125") (name "unconnected-(U900C-RFU-PadE5)") (class "Default")
      (node (ref "U900") (pin "E5") (pinfunction "RFU_E5") (pintype "passive+no_connect"))
    )
    (net (code "126") (name "unconnected-(U900C-RFU-PadE8)") (class "Default")
      (node (ref "U900") (pin "E8") (pinfunction "RFU_E8") (pintype "passive+no_connect"))
    )
    (net (code "127") (name "unconnected-(U900C-RFU-PadE9)") (class "Default")
      (node (ref "U900") (pin "E9") (pinfunction "RFU_E9") (pintype "passive+no_connect"))
    )
    (net (code "128") (name "unconnected-(U900C-RFU-PadE10)") (class "Default")
      (node (ref "U900") (pin "E10") (pinfunction "RFU_E10") (pintype "passive+no_connect"))
    )
    (net (code "129") (name "unconnected-(U900C-RFU-PadF10)") (class "Default")
      (node (ref "U900") (pin "F10") (pinfunction "RFU_F10") (pintype "passive+no_connect"))
    )
    (net (code "130") (name "unconnected-(U900C-RFU-PadG3)") (class "Default")
      (node (ref "U900") (pin "G3") (pinfunction "RFU_G3") (pintype "passive+no_connect"))
    )
    (net (code "131") (name "unconnected-(U900C-RFU-PadG10)") (class "Default")
      (node (ref "U900") (pin "G10") (pinfunction "RFU_G10") (pintype "passive+no_connect"))
    )
    (net (code "132") (name "unconnected-(U900C-RFU-PadK6)") (class "Default")
      (node (ref "U900") (pin "K6") (pinfunction "RFU_K6") (pintype "passive+no_connect"))
    )
    (net (code "133") (name "unconnected-(U900C-RFU-PadK7)") (class "Default")
      (node (ref "U900") (pin "K7") (pinfunction "RFU_K7") (pintype "passive+no_connect"))
    )
    (net (code "134") (name "unconnected-(U900C-RFU-PadK10)") (class "Default")
      (node (ref "U900") (pin "K10") (pinfunction "RFU_K10") (pintype "passive+no_connect"))
    )
    (net (code "135") (name "unconnected-(U900C-RFU-PadP10)") (class "Default")
      (node (ref "U900") (pin "P10") (pinfunction "RFU_P10") (pintype "passive+no_connect"))
    )
  )
)
